# Sheet1.net
KiCad netlist of a schematic drawn in Altium Designer
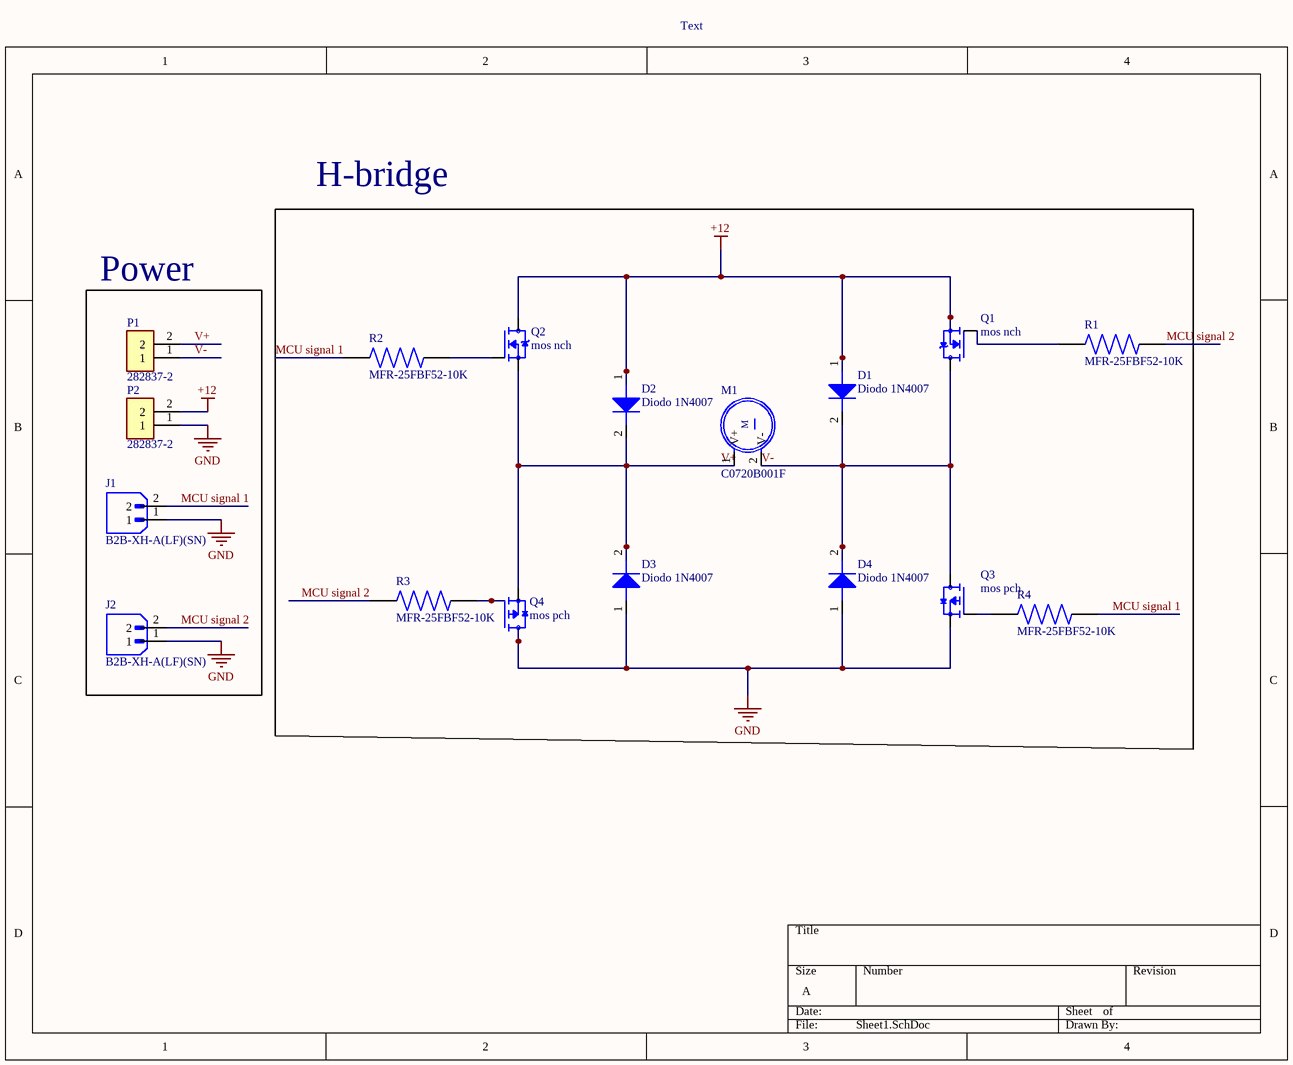
[diagram p0: Sheet1.SchDoc]

(export (version "E")
  (design (tool "Eeschema 10.0.6"))
  (components
    (comp (ref "D1")
      (value "Diodo 1N4007")
      (footprint "Diodo 1N4007")
      (libsource (lib "Schlib1") (part "Diodo 1N4007"))
    )
    (comp (ref "D2")
      (value "Diodo 1N4007")
      (footprint "Diodo 1N4007")
      (libsource (lib "Schlib1") (part "Diodo 1N4007"))
    )
    (comp (ref "D3")
      (value "Diodo 1N4007")
      (footprint "Diodo 1N4007")
      (libsource (lib "Schlib1") (part "Diodo 1N4007"))
    )
    (comp (ref "D4")
      (value "Diodo 1N4007")
      (footprint "Diodo 1N4007")
      (libsource (lib "Schlib1") (part "Diodo 1N4007"))
    )
    (comp (ref "J1")
      (value "B2B-XH-A(LF)(SN)")
      (footprint "JST_B2B-XH-A(LF)(SN)")
      (description "Connector Header Through Hole 2 position 0.098 (2.50mm)")
      (fields (field (name "MF") "JST Sales America Inc."))
      (libsource (lib "Schlib1") (part "B2B-XH-A(LF)(SN)"))
    )
    (comp (ref "J2")
      (value "B2B-XH-A(LF)(SN)")
      (footprint "JST_B2B-XH-A(LF)(SN)")
      (description "Connector Header Through Hole 2 position 0.098 (2.50mm)")
      (fields (field (name "MF") "JST Sales America Inc."))
      (libsource (lib "Schlib1") (part "B2B-XH-A(LF)(SN)"))
    )
    (comp (ref "M1")
      (value "C0720B001F")
      (footprint "XDCR_C0720B001F")
      (description "DC Motor Vibration, ERM 10000 RPM 3VDC")
      (fields (field (name "MF") "Jinlong Machinery"))
      (libsource (lib "Schlib1") (part "C0720B001F"))
    )
    (comp (ref "P1")
      (value "282837-2")
      (footprint "TE_282837-2")
      (fields (field (name "MF") "TE Connectivity"))
      (libsource (lib "Schlib1") (part "282837-2"))
    )
    (comp (ref "P2")
      (value "282837-2")
      (footprint "TE_282837-2")
      (fields (field (name "MF") "TE Connectivity"))
      (libsource (lib "Schlib1") (part "282837-2"))
    )
    (comp (ref "Q1")
      (value "mos nch")
      (footprint "mos nch")
      (description "N-Channel 55 V 75A (Tc) 170W (Tc) Through Hole TO-220AB")
      (fields (field (name "MP") "IRF3205ZPBF") (field (name "MF") "Infineon Technologies"))
      (libsource (lib "Schlib1") (part "mos nch"))
    )
    (comp (ref "Q2")
      (value "mos nch")
      (footprint "mos nch")
      (description "N-Channel 55 V 75A (Tc) 170W (Tc) Through Hole TO-220AB")
      (fields (field (name "MP") "IRF3205ZPBF") (field (name "MF") "Infineon Technologies"))
      (libsource (lib "Schlib1") (part "mos nch"))
    )
    (comp (ref "Q3")
      (value "mos pch")
      (footprint "mos pch")
      (fields (field (name "MP") "IRF9540NPBF") (field (name "MF") "Infineon Technologies"))
      (libsource (lib "Schlib1") (part "mos pch"))
    )
    (comp (ref "Q4")
      (value "mos pch")
      (footprint "mos pch")
      (fields (field (name "MP") "IRF9540NPBF") (field (name "MF") "Infineon Technologies"))
      (libsource (lib "Schlib1") (part "mos pch"))
    )
    (comp (ref "R1")
      (value "MFR-25FBF52-10K")
      (footprint "RESAD1100W55L680D260")
      (description "10.2 kOhms Â±1% 0.25W, 1/4W Through Hole Resistor Axial - Metal Film")
      (fields (field (name "MF") "Yageo"))
      (libsource (lib "Schlib1") (part "MFR-25FBF52-10K"))
    )
    (comp (ref "R2")
      (value "MFR-25FBF52-10K")
      (footprint "RESAD1100W55L680D260")
      (description "10.2 kOhms Â±1% 0.25W, 1/4W Through Hole Resistor Axial - Metal Film")
      (fields (field (name "MF") "Yageo"))
      (libsource (lib "Schlib1") (part "MFR-25FBF52-10K"))
    )
    (comp (ref "R3")
      (value "MFR-25FBF52-10K")
      (footprint "RESAD1100W55L680D260")
      (description "10.2 kOhms Â±1% 0.25W, 1/4W Through Hole Resistor Axial - Metal Film")
      (fields (field (name "MF") "Yageo"))
      (libsource (lib "Schlib1") (part "MFR-25FBF52-10K"))
    )
    (comp (ref "R4")
      (value "MFR-25FBF52-10K")
      (footprint "RESAD1100W55L680D260")
      (description "10.2 kOhms Â±1% 0.25W, 1/4W Through Hole Resistor Axial - Metal Film")
      (fields (field (name "MF") "Yageo"))
      (libsource (lib "Schlib1") (part "MFR-25FBF52-10K"))
    )
  )
  (nets
    (net (code "1") (name "+12") (class "Default")
      (node (ref "D1") (pin "1") (pinfunction "1_1") (pintype "passive"))
      (node (ref "D2") (pin "1") (pinfunction "1_1") (pintype "passive"))
      (node (ref "P2") (pin "2") (pinfunction "2_2") (pintype "passive"))
      (node (ref "Q1") (pin "3") (pinfunction "S_3") (pintype "passive"))
      (node (ref "Q2") (pin "2") (pinfunction "D_2") (pintype "passive"))
    )
    (net (code "2") (name "/MCU signal 1") (class "Default")
      (node (ref "J1") (pin "2") (pinfunction "2_2") (pintype "passive"))
      (node (ref "R2") (pin "1") (pinfunction "1_1") (pintype "passive"))
      (node (ref "R4") (pin "2") (pinfunction "2_2") (pintype "passive"))
    )
    (net (code "3") (name "/MCU signal 2") (class "Default")
      (node (ref "J2") (pin "2") (pinfunction "2_2") (pintype "passive"))
      (node (ref "R1") (pin "2") (pinfunction "2_2") (pintype "passive"))
      (node (ref "R3") (pin "1") (pinfunction "1_1") (pintype "passive"))
    )
    (net (code "4") (name "/V+") (class "Default")
      (node (ref "D2") (pin "2") (pinfunction "2_2") (pintype "passive"))
      (node (ref "D3") (pin "2") (pinfunction "2_2") (pintype "passive"))
      (node (ref "M1") (pin "1") (pinfunction "V+_1") (pintype "power_in"))
      (node (ref "P1") (pin "2") (pinfunction "2_2") (pintype "passive"))
      (node (ref "Q2") (pin "3") (pinfunction "S_3") (pintype "passive"))
      (node (ref "Q4") (pin "3") (pinfunction "S_3") (pintype "passive"))
    )
    (net (code "5") (name "/V-") (class "Default")
      (node (ref "D1") (pin "2") (pinfunction "2_2") (pintype "passive"))
      (node (ref "D4") (pin "2") (pinfunction "2_2") (pintype "passive"))
      (node (ref "M1") (pin "2") (pinfunction "V-_2") (pintype "power_in"))
      (node (ref "P1") (pin "1") (pinfunction "1_1") (pintype "passive"))
      (node (ref "Q1") (pin "2") (pinfunction "D_2") (pintype "passive"))
      (node (ref "Q3") (pin "2") (pinfunction "D_2") (pintype "passive"))
    )
    (net (code "6") (name "GND") (class "Default")
      (node (ref "D3") (pin "1") (pinfunction "1_1") (pintype "passive"))
      (node (ref "D4") (pin "1") (pinfunction "1_1") (pintype "passive"))
      (node (ref "J1") (pin "1") (pinfunction "1_1") (pintype "passive"))
      (node (ref "J2") (pin "1") (pinfunction "1_1") (pintype "passive"))
      (node (ref "P2") (pin "1") (pinfunction "1_1") (pintype "passive"))
      (node (ref "Q3") (pin "3") (pinfunction "S_3") (pintype "passive"))
      (node (ref "Q4") (pin "2") (pinfunction "D_2") (pintype "passive"))
    )
    (net (code "7") (name "Net-(Q1-G)") (class "Default")
      (node (ref "Q1") (pin "1") (pinfunction "G_1") (pintype "passive"))
      (node (ref "R1") (pin "1") (pinfunction "1_1") (pintype "passive"))
    )
    (net (code "8") (name "Net-(Q2-G)") (class "Default")
      (node (ref "Q2") (pin "1") (pinfunction "G_1") (pintype "passive"))
      (node (ref "R2") (pin "2") (pinfunction "2_2") (pintype "passive"))
    )
    (net (code "9") (name "Net-(Q3-G)") (class "Default")
      (node (ref "Q3") (pin "1") (pinfunction "G_1") (pintype "passive"))
      (node (ref "R4") (pin "1") (pinfunction "1_1") (pintype "passive"))
    )
    (net (code "10") (name "Net-(Q4-G)") (class "Default")
      (node (ref "Q4") (pin "1") (pinfunction "G_1") (pintype "passive"))
      (node (ref "R3") (pin "2") (pinfunction "2_2") (pintype "passive"))
    )
  )
)
